# BumpSensors.net
KiCad netlist of a schematic drawn in Altium Designer
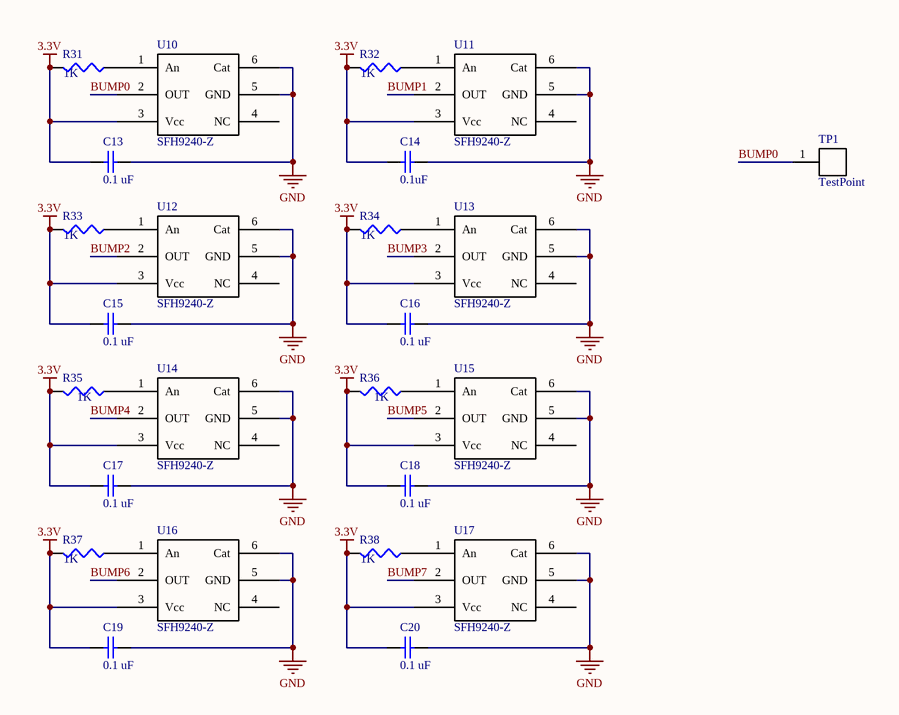
[diagram p0: BumpSensors.SchDoc]

(export (version "E")
  (design (tool "Eeschema 10.0.6"))
  (components
    (comp (ref "C13")
      (value "0.1 uF")
      (footprint "CAPC1005L")
      (description "Capacitor (Semiconductor SIM Model)")
      (fields (field (name "Comment") "Cap Semi") (field (name "PUBLISHER") "Altium Limited"))
      (libsource (lib "Miscellaneous Devices") (part "Cap Semi"))
    )
    (comp (ref "C14")
      (value "0.1uF")
      (footprint "CAPC1005L")
      (description "Capacitor (Semiconductor SIM Model)")
      (fields (field (name "Comment") "Cap Semi") (field (name "PUBLISHER") "Altium Limited"))
      (libsource (lib "Miscellaneous Devices") (part "Cap Semi"))
    )
    (comp (ref "C15")
      (value "0.1 uF")
      (footprint "CAPC1005L")
      (description "Capacitor (Semiconductor SIM Model)")
      (fields (field (name "Comment") "Cap Semi") (field (name "PUBLISHER") "Altium Limited"))
      (libsource (lib "Miscellaneous Devices") (part "Cap Semi"))
    )
    (comp (ref "C16")
      (value "0.1 uF")
      (footprint "CAPC1005L")
      (description "Capacitor (Semiconductor SIM Model)")
      (fields (field (name "Comment") "Cap Semi") (field (name "PUBLISHER") "Altium Limited"))
      (libsource (lib "Miscellaneous Devices") (part "Cap Semi"))
    )
    (comp (ref "C17")
      (value "0.1 uF")
      (footprint "CAPC1005L")
      (description "Capacitor (Semiconductor SIM Model)")
      (fields (field (name "Comment") "Cap Semi") (field (name "PUBLISHER") "Altium Limited"))
      (libsource (lib "Miscellaneous Devices") (part "Cap Semi"))
    )
    (comp (ref "C18")
      (value "0.1 uF")
      (footprint "CAPC1005L")
      (description "Capacitor (Semiconductor SIM Model)")
      (fields (field (name "Comment") "Cap Semi") (field (name "PUBLISHER") "Altium Limited"))
      (libsource (lib "Miscellaneous Devices") (part "Cap Semi"))
    )
    (comp (ref "C19")
      (value "0.1 uF")
      (footprint "CAPC1005L")
      (description "Capacitor (Semiconductor SIM Model)")
      (fields (field (name "Comment") "Cap Semi") (field (name "PUBLISHER") "Altium Limited"))
      (libsource (lib "Miscellaneous Devices") (part "Cap Semi"))
    )
    (comp (ref "C20")
      (value "0.1 uF")
      (footprint "CAPC1005L")
      (description "Capacitor (Semiconductor SIM Model)")
      (fields (field (name "Comment") "Cap Semi") (field (name "PUBLISHER") "Altium Limited"))
      (libsource (lib "Miscellaneous Devices") (part "Cap Semi"))
    )
    (comp (ref "R31")
      (value "1K")
      (footprint "RESC1608L")
      (description "Resistor")
      (fields (field (name "Comment") "Res3") (field (name "PUBLISHER") "Altium Limited"))
      (libsource (lib "Miscellaneous Devices") (part "Res3"))
    )
    (comp (ref "R32")
      (value "1K")
      (footprint "RESC1608L")
      (description "Resistor")
      (fields (field (name "Comment") "Res3") (field (name "PUBLISHER") "Altium Limited"))
      (libsource (lib "Miscellaneous Devices") (part "Res3"))
    )
    (comp (ref "R33")
      (value "1K")
      (footprint "RESC1608L")
      (description "Resistor")
      (fields (field (name "Comment") "Res3") (field (name "PUBLISHER") "Altium Limited"))
      (libsource (lib "Miscellaneous Devices") (part "Res3"))
    )
    (comp (ref "R34")
      (value "1K")
      (footprint "RESC1608L")
      (description "Resistor")
      (fields (field (name "Comment") "Res3") (field (name "PUBLISHER") "Altium Limited"))
      (libsource (lib "Miscellaneous Devices") (part "Res3"))
    )
    (comp (ref "R35")
      (value "1K")
      (footprint "RESC1608L")
      (description "Resistor")
      (fields (field (name "Comment") "Res3") (field (name "PUBLISHER") "Altium Limited"))
      (libsource (lib "Miscellaneous Devices") (part "Res3"))
    )
    (comp (ref "R36")
      (value "1K")
      (footprint "RESC1608L")
      (description "Resistor")
      (fields (field (name "Comment") "Res3") (field (name "PUBLISHER") "Altium Limited"))
      (libsource (lib "Miscellaneous Devices") (part "Res3"))
    )
    (comp (ref "R37")
      (value "1K")
      (footprint "RESC1608L")
      (description "Resistor")
      (fields (field (name "Comment") "Res3") (field (name "PUBLISHER") "Altium Limited"))
      (libsource (lib "Miscellaneous Devices") (part "Res3"))
    )
    (comp (ref "R38")
      (value "1K")
      (footprint "RESC1608L")
      (description "Resistor")
      (fields (field (name "Comment") "Res3") (field (name "PUBLISHER") "Altium Limited"))
      (libsource (lib "Miscellaneous Devices") (part "Res3"))
    )
    (comp (ref "TP1")
      (value "TestPoint")
      (footprint "TestPoint")
      (libsource (lib "mrone") (part "TestPoint"))
    )
    (comp (ref "U10")
      (value "SFH9240-Z")
      (footprint "SFH9240-Z")
      (libsource (lib "mrone") (part "SFH9240-Z"))
    )
    (comp (ref "U11")
      (value "SFH9240-Z")
      (footprint "SFH9240-Z")
      (libsource (lib "mrone") (part "SFH9240-Z"))
    )
    (comp (ref "U12")
      (value "SFH9240-Z")
      (footprint "SFH9240-Z")
      (libsource (lib "mrone") (part "SFH9240-Z"))
    )
    (comp (ref "U13")
      (value "SFH9240-Z")
      (footprint "SFH9240-Z")
      (libsource (lib "mrone") (part "SFH9240-Z"))
    )
    (comp (ref "U14")
      (value "SFH9240-Z")
      (footprint "SFH9240-Z")
      (libsource (lib "mrone") (part "SFH9240-Z"))
    )
    (comp (ref "U15")
      (value "SFH9240-Z")
      (footprint "SFH9240-Z")
      (libsource (lib "mrone") (part "SFH9240-Z"))
    )
    (comp (ref "U16")
      (value "SFH9240-Z")
      (footprint "SFH9240-Z")
      (libsource (lib "mrone") (part "SFH9240-Z"))
    )
    (comp (ref "U17")
      (value "SFH9240-Z")
      (footprint "SFH9240-Z")
      (libsource (lib "mrone") (part "SFH9240-Z"))
    )
  )
  (nets
    (net (code "1") (name "/BUMP0") (class "Default")
      (node (ref "TP1") (pin "1") (pintype "passive"))
      (node (ref "U10") (pin "2") (pinfunction "OUT_2") (pintype "passive"))
    )
    (net (code "2") (name "/BUMP1") (class "Default")
      (node (ref "U11") (pin "2") (pinfunction "OUT_2") (pintype "passive"))
    )
    (net (code "3") (name "/BUMP2") (class "Default")
      (node (ref "U12") (pin "2") (pinfunction "OUT_2") (pintype "passive"))
    )
    (net (code "4") (name "/BUMP3") (class "Default")
      (node (ref "U13") (pin "2") (pinfunction "OUT_2") (pintype "passive"))
    )
    (net (code "5") (name "/BUMP4") (class "Default")
      (node (ref "U14") (pin "2") (pinfunction "OUT_2") (pintype "passive"))
    )
    (net (code "6") (name "/BUMP5") (class "Default")
      (node (ref "U15") (pin "2") (pinfunction "OUT_2") (pintype "passive"))
    )
    (net (code "7") (name "/BUMP6") (class "Default")
      (node (ref "U16") (pin "2") (pinfunction "OUT_2") (pintype "passive"))
    )
    (net (code "8") (name "/BUMP7") (class "Default")
      (node (ref "U17") (pin "2") (pinfunction "OUT_2") (pintype "passive"))
    )
    (net (code "9") (name "3.3V") (class "Default")
      (node (ref "C13") (pin "2") (pinfunction "2_2") (pintype "passive"))
      (node (ref "C14") (pin "2") (pinfunction "2_2") (pintype "passive"))
      (node (ref "C15") (pin "2") (pinfunction "2_2") (pintype "passive"))
      (node (ref "C16") (pin "2") (pinfunction "2_2") (pintype "passive"))
      (node (ref "C17") (pin "2") (pinfunction "2_2") (pintype "passive"))
      (node (ref "C18") (pin "2") (pinfunction "2_2") (pintype "passive"))
      (node (ref "C19") (pin "2") (pinfunction "2_2") (pintype "passive"))
      (node (ref "C20") (pin "2") (pinfunction "2_2") (pintype "passive"))
      (node (ref "R31") (pin "2") (pinfunction "2_2") (pintype "passive"))
      (node (ref "R32") (pin "2") (pinfunction "2_2") (pintype "passive"))
      (node (ref "R33") (pin "2") (pinfunction "2_2") (pintype "passive"))
      (node (ref "R34") (pin "2") (pinfunction "2_2") (pintype "passive"))
      (node (ref "R35") (pin "2") (pinfunction "2_2") (pintype "passive"))
      (node (ref "R36") (pin "2") (pinfunction "2_2") (pintype "passive"))
      (node (ref "R37") (pin "2") (pinfunction "2_2") (pintype "passive"))
      (node (ref "R38") (pin "2") (pinfunction "2_2") (pintype "passive"))
      (node (ref "U10") (pin "3") (pinfunction "Vcc_3") (pintype "passive"))
      (node (ref "U11") (pin "3") (pinfunction "Vcc_3") (pintype "passive"))
      (node (ref "U12") (pin "3") (pinfunction "Vcc_3") (pintype "passive"))
      (node (ref "U13") (pin "3") (pinfunction "Vcc_3") (pintype "passive"))
      (node (ref "U14") (pin "3") (pinfunction "Vcc_3") (pintype "passive"))
      (node (ref "U15") (pin "3") (pinfunction "Vcc_3") (pintype "passive"))
      (node (ref "U16") (pin "3") (pinfunction "Vcc_3") (pintype "passive"))
      (node (ref "U17") (pin "3") (pinfunction "Vcc_3") (pintype "passive"))
    )
    (net (code "10") (name "GND") (class "Default")
      (node (ref "C13") (pin "1") (pinfunction "1_1") (pintype "passive"))
      (node (ref "C14") (pin "1") (pinfunction "1_1") (pintype "passive"))
      (node (ref "C15") (pin "1") (pinfunction "1_1") (pintype "passive"))
      (node (ref "C16") (pin "1") (pinfunction "1_1") (pintype "passive"))
      (node (ref "C17") (pin "1") (pinfunction "1_1") (pintype "passive"))
      (node (ref "C18") (pin "1") (pinfunction "1_1") (pintype "passive"))
      (node (ref "C19") (pin "1") (pinfunction "1_1") (pintype "passive"))
      (node (ref "C20") (pin "1") (pinfunction "1_1") (pintype "passive"))
      (node (ref "U10") (pin "5") (pinfunction "GND_5") (pintype "passive"))
      (node (ref "U10") (pin "6") (pinfunction "Cat_6") (pintype "passive"))
      (node (ref "U11") (pin "5") (pinfunction "GND_5") (pintype "passive"))
      (node (ref "U11") (pin "6") (pinfunction "Cat_6") (pintype "passive"))
      (node (ref "U12") (pin "5") (pinfunction "GND_5") (pintype "passive"))
      (node (ref "U12") (pin "6") (pinfunction "Cat_6") (pintype "passive"))
      (node (ref "U13") (pin "5") (pinfunction "GND_5") (pintype "passive"))
      (node (ref "U13") (pin "6") (pinfunction "Cat_6") (pintype "passive"))
      (node (ref "U14") (pin "5") (pinfunction "GND_5") (pintype "passive"))
      (node (ref "U14") (pin "6") (pinfunction "Cat_6") (pintype "passive"))
      (node (ref "U15") (pin "5") (pinfunction "GND_5") (pintype "passive"))
      (node (ref "U15") (pin "6") (pinfunction "Cat_6") (pintype "passive"))
      (node (ref "U16") (pin "5") (pinfunction "GND_5") (pintype "passive"))
      (node (ref "U16") (pin "6") (pinfunction "Cat_6") (pintype "passive"))
      (node (ref "U17") (pin "5") (pinfunction "GND_5") (pintype "passive"))
      (node (ref "U17") (pin "6") (pinfunction "Cat_6") (pintype "passive"))
    )
    (net (code "11") (name "Net-(U10-An)") (class "Default")
      (node (ref "R31") (pin "1") (pinfunction "1_1") (pintype "passive"))
      (node (ref "U10") (pin "1") (pinfunction "An_1") (pintype "passive"))
    )
    (net (code "12") (name "Net-(U11-An)") (class "Default")
      (node (ref "R32") (pin "1") (pinfunction "1_1") (pintype "passive"))
      (node (ref "U11") (pin "1") (pinfunction "An_1") (pintype "passive"))
    )
    (net (code "13") (name "Net-(U12-An)") (class "Default")
      (node (ref "R33") (pin "1") (pinfunction "1_1") (pintype "passive"))
      (node (ref "U12") (pin "1") (pinfunction "An_1") (pintype "passive"))
    )
    (net (code "14") (name "Net-(U13-An)") (class "Default")
      (node (ref "R34") (pin "1") (pinfunction "1_1") (pintype "passive"))
      (node (ref "U13") (pin "1") (pinfunction "An_1") (pintype "passive"))
    )
    (net (code "15") (name "Net-(U14-An)") (class "Default")
      (node (ref "R35") (pin "1") (pinfunction "1_1") (pintype "passive"))
      (node (ref "U14") (pin "1") (pinfunction "An_1") (pintype "passive"))
    )
    (net (code "16") (name "Net-(U15-An)") (class "Default")
      (node (ref "R36") (pin "1") (pinfunction "1_1") (pintype "passive"))
      (node (ref "U15") (pin "1") (pinfunction "An_1") (pintype "passive"))
    )
    (net (code "17") (name "Net-(U16-An)") (class "Default")
      (node (ref "R37") (pin "1") (pinfunction "1_1") (pintype "passive"))
      (node (ref "U16") (pin "1") (pinfunction "An_1") (pintype "passive"))
    )
    (net (code "18") (name "Net-(U17-An)") (class "Default")
      (node (ref "R38") (pin "1") (pinfunction "1_1") (pintype "passive"))
      (node (ref "U17") (pin "1") (pinfunction "An_1") (pintype "passive"))
    )
    (net (code "19") (name "unconnected-(U10-NC-Pad4)") (class "Default")
      (node (ref "U10") (pin "4") (pinfunction "NC_4") (pintype "passive"))
    )
    (net (code "20") (name "unconnected-(U11-NC-Pad4)") (class "Default")
      (node (ref "U11") (pin "4") (pinfunction "NC_4") (pintype "passive"))
    )
    (net (code "21") (name "unconnected-(U12-NC-Pad4)") (class "Default")
      (node (ref "U12") (pin "4") (pinfunction "NC_4") (pintype "passive"))
    )
    (net (code "22") (name "unconnected-(U13-NC-Pad4)") (class "Default")
      (node (ref "U13") (pin "4") (pinfunction "NC_4") (pintype "passive"))
    )
    (net (code "23") (name "unconnected-(U14-NC-Pad4)") (class "Default")
      (node (ref "U14") (pin "4") (pinfunction "NC_4") (pintype "passive"))
    )
    (net (code "24") (name "unconnected-(U15-NC-Pad4)") (class "Default")
      (node (ref "U15") (pin "4") (pinfunction "NC_4") (pintype "passive"))
    )
    (net (code "25") (name "unconnected-(U16-NC-Pad4)") (class "Default")
      (node (ref "U16") (pin "4") (pinfunction "NC_4") (pintype "passive"))
    )
    (net (code "26") (name "unconnected-(U17-NC-Pad4)") (class "Default")
      (node (ref "U17") (pin "4") (pinfunction "NC_4") (pintype "passive"))
    )
  )
)
